# AS3364_DG412_bus_mixer_v1_3.net
KiCad netlist of a schematic drawn in EAGLE
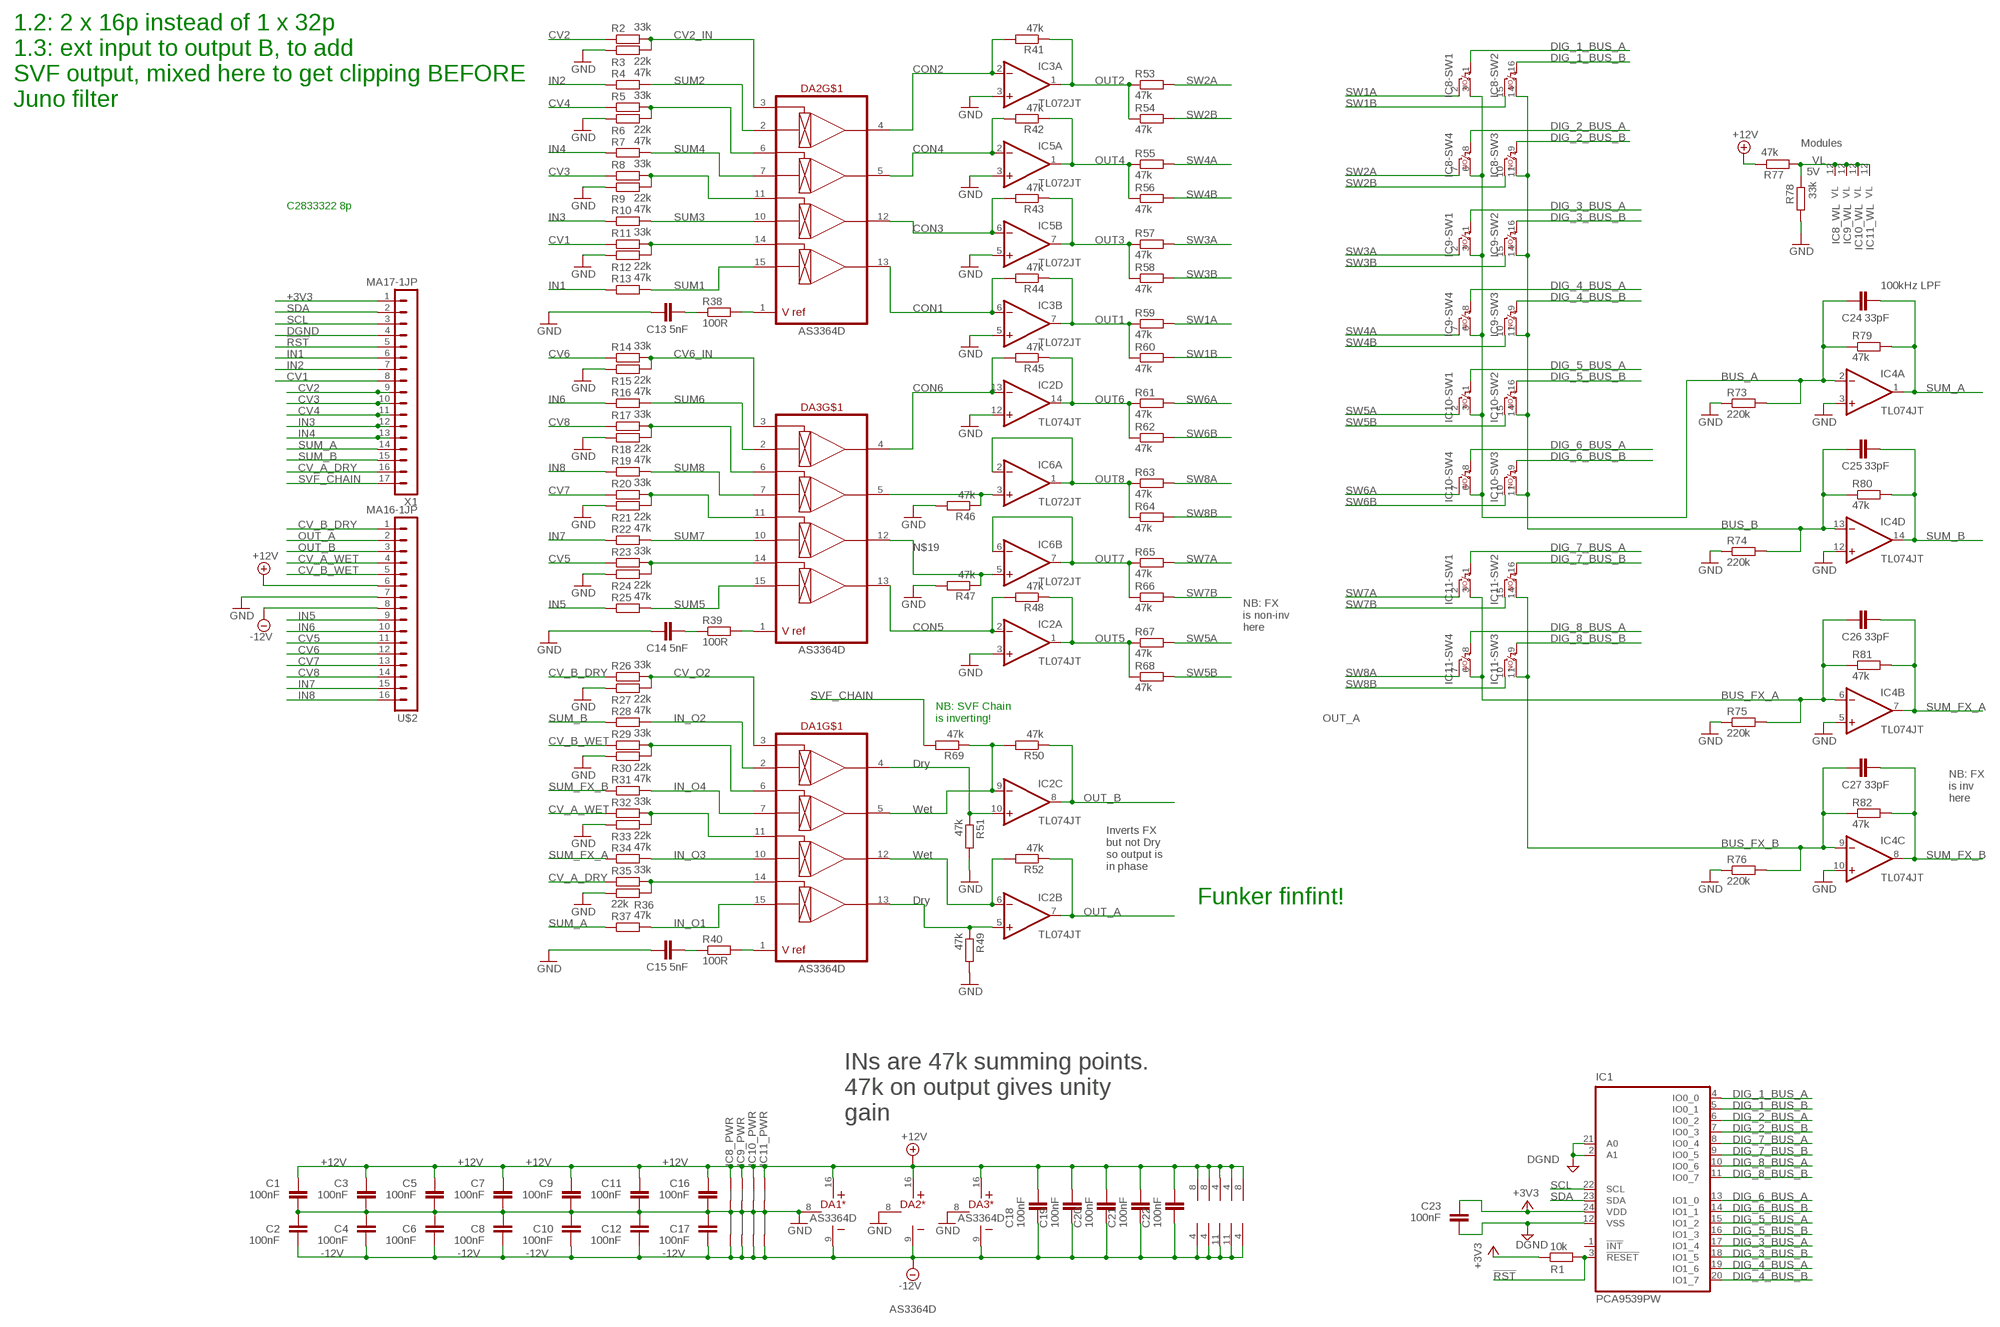
[diagram p0: schematic, sheet 1]

(export (version "E")
  (design (tool "Eeschema 10.0.6"))
  (components
    (comp (ref "C1")
      (value "100nF")
      (footprint "eagle-import:C0402")
      (libsource (lib "eagle-import") (part "C-EUC0402"))
    )
    (comp (ref "C2")
      (value "100nF")
      (footprint "eagle-import:C0402")
      (libsource (lib "eagle-import") (part "C-EUC0402"))
    )
    (comp (ref "C3")
      (value "100nF")
      (footprint "eagle-import:C0402")
      (libsource (lib "eagle-import") (part "C-EUC0402"))
    )
    (comp (ref "C4")
      (value "100nF")
      (footprint "eagle-import:C0402")
      (libsource (lib "eagle-import") (part "C-EUC0402"))
    )
    (comp (ref "C5")
      (value "100nF")
      (footprint "eagle-import:C0402")
      (libsource (lib "eagle-import") (part "C-EUC0402"))
    )
    (comp (ref "C6")
      (value "100nF")
      (footprint "eagle-import:C0402")
      (libsource (lib "eagle-import") (part "C-EUC0402"))
    )
    (comp (ref "C7")
      (value "100nF")
      (footprint "eagle-import:C0402")
      (libsource (lib "eagle-import") (part "C-EUC0402"))
    )
    (comp (ref "C8")
      (value "100nF")
      (footprint "eagle-import:C0402")
      (libsource (lib "eagle-import") (part "C-EUC0402"))
    )
    (comp (ref "C9")
      (value "100nF")
      (footprint "eagle-import:C0402")
      (libsource (lib "eagle-import") (part "C-EUC0402"))
    )
    (comp (ref "C10")
      (value "100nF")
      (footprint "eagle-import:C0402")
      (libsource (lib "eagle-import") (part "C-EUC0402"))
    )
    (comp (ref "C11")
      (value "100nF")
      (footprint "eagle-import:C0402")
      (libsource (lib "eagle-import") (part "C-EUC0402"))
    )
    (comp (ref "C12")
      (value "100nF")
      (footprint "eagle-import:C0402")
      (libsource (lib "eagle-import") (part "C-EUC0402"))
    )
    (comp (ref "C13")
      (value "5nF")
      (footprint "eagle-import:C0402-J")
      (libsource (lib "eagle-import") (part "C-EU-J"))
    )
    (comp (ref "C14")
      (value "5nF")
      (footprint "eagle-import:C0402-J")
      (libsource (lib "eagle-import") (part "C-EU-J"))
    )
    (comp (ref "C15")
      (value "5nF")
      (footprint "eagle-import:C0402-J")
      (libsource (lib "eagle-import") (part "C-EU-J"))
    )
    (comp (ref "C16")
      (value "100nF")
      (footprint "eagle-import:C0402")
      (libsource (lib "eagle-import") (part "C-EUC0402"))
    )
    (comp (ref "C17")
      (value "100nF")
      (footprint "eagle-import:C0402")
      (libsource (lib "eagle-import") (part "C-EUC0402"))
    )
    (comp (ref "C18")
      (value "100nF")
      (footprint "eagle-import:C0402")
      (libsource (lib "eagle-import") (part "C-EUC0402"))
    )
    (comp (ref "C19")
      (value "100nF")
      (footprint "eagle-import:C0402")
      (libsource (lib "eagle-import") (part "C-EUC0402"))
    )
    (comp (ref "C20")
      (value "100nF")
      (footprint "eagle-import:C0402")
      (libsource (lib "eagle-import") (part "C-EUC0402"))
    )
    (comp (ref "C21")
      (value "100nF")
      (footprint "eagle-import:C0402")
      (libsource (lib "eagle-import") (part "C-EUC0402"))
    )
    (comp (ref "C22")
      (value "100nF")
      (footprint "eagle-import:C0402")
      (libsource (lib "eagle-import") (part "C-EUC0402"))
    )
    (comp (ref "C23")
      (value "100nF")
      (footprint "eagle-import:C0402")
      (libsource (lib "eagle-import") (part "C-EUC0402"))
    )
    (comp (ref "C24")
      (value "33pF")
      (footprint "eagle-import:C0402-J")
      (libsource (lib "eagle-import") (part "C-EU-J"))
    )
    (comp (ref "C25")
      (value "33pF")
      (footprint "eagle-import:C0402-J")
      (libsource (lib "eagle-import") (part "C-EU-J"))
    )
    (comp (ref "C26")
      (value "33pF")
      (footprint "eagle-import:C0402-J")
      (libsource (lib "eagle-import") (part "C-EU-J"))
    )
    (comp (ref "C27")
      (value "33pF")
      (footprint "eagle-import:C0402-J")
      (libsource (lib "eagle-import") (part "C-EU-J"))
    )
    (comp (ref "DA1")
      (value "AS3364D")
      (footprint "eagle-import:DIL16J")
      (libsource (lib "eagle-import") (part "AS3364D"))
    )
    (comp (ref "DA2")
      (value "AS3364D")
      (footprint "eagle-import:DIL16J")
      (libsource (lib "eagle-import") (part "AS3364D"))
    )
    (comp (ref "DA3")
      (value "AS3364D")
      (footprint "eagle-import:DIL16J")
      (libsource (lib "eagle-import") (part "AS3364D"))
    )
    (comp (ref "IC1")
      (value "PCA9539PW")
      (footprint "eagle-import:TSSOP24J")
      (libsource (lib "eagle-import") (part "PCA9539PW"))
    )
    (comp (ref "IC2")
      (value "TL074JT")
      (footprint "eagle-import:TSSOP14J")
      (libsource (lib "eagle-import") (part "TL074JT"))
    )
    (comp (ref "IC3")
      (value "TL072JT")
      (footprint "eagle-import:TSSOP8J")
      (libsource (lib "eagle-import") (part "TL072JT"))
    )
    (comp (ref "IC4")
      (value "TL074JT")
      (footprint "eagle-import:TSSOP14J")
      (libsource (lib "eagle-import") (part "TL074JT"))
    )
    (comp (ref "IC5")
      (value "TL072JT")
      (footprint "eagle-import:TSSOP8J")
      (libsource (lib "eagle-import") (part "TL072JT"))
    )
    (comp (ref "IC6")
      (value "TL072JT")
      (footprint "eagle-import:TSSOP8J")
      (libsource (lib "eagle-import") (part "TL072JT"))
    )
    (comp (ref "IC8")
      (value "DG412-J")
      (footprint "eagle-import:DIL16J")
      (libsource (lib "eagle-import") (part "DG412-J"))
    )
    (comp (ref "IC9")
      (value "DG412-J")
      (footprint "eagle-import:DIL16J")
      (libsource (lib "eagle-import") (part "DG412-J"))
    )
    (comp (ref "IC10")
      (value "DG412-J")
      (footprint "eagle-import:DIL16J")
      (libsource (lib "eagle-import") (part "DG412-J"))
    )
    (comp (ref "IC11")
      (value "DG412-J")
      (footprint "eagle-import:DIL16J")
      (libsource (lib "eagle-import") (part "DG412-J"))
    )
    (comp (ref "R1")
      (value "10k")
      (footprint "eagle-import:R0402")
      (libsource (lib "eagle-import") (part "R-EU_R0402"))
    )
    (comp (ref "R2")
      (value "33k")
      (footprint "eagle-import:R0402")
      (libsource (lib "eagle-import") (part "R-EU_R0402"))
    )
    (comp (ref "R3")
      (value "22k")
      (footprint "eagle-import:R0402")
      (libsource (lib "eagle-import") (part "R-EU_R0402"))
    )
    (comp (ref "R4")
      (value "47k")
      (footprint "eagle-import:R0402")
      (libsource (lib "eagle-import") (part "R-EU_R0402"))
    )
    (comp (ref "R5")
      (value "33k")
      (footprint "eagle-import:R0402")
      (libsource (lib "eagle-import") (part "R-EU_R0402"))
    )
    (comp (ref "R6")
      (value "22k")
      (footprint "eagle-import:R0402")
      (libsource (lib "eagle-import") (part "R-EU_R0402"))
    )
    (comp (ref "R7")
      (value "47k")
      (footprint "eagle-import:R0402")
      (libsource (lib "eagle-import") (part "R-EU_R0402"))
    )
    (comp (ref "R8")
      (value "33k")
      (footprint "eagle-import:R0402")
      (libsource (lib "eagle-import") (part "R-EU_R0402"))
    )
    (comp (ref "R9")
      (value "22k")
      (footprint "eagle-import:R0402")
      (libsource (lib "eagle-import") (part "R-EU_R0402"))
    )
    (comp (ref "R10")
      (value "47k")
      (footprint "eagle-import:R0402")
      (libsource (lib "eagle-import") (part "R-EU_R0402"))
    )
    (comp (ref "R11")
      (value "33k")
      (footprint "eagle-import:R0402")
      (libsource (lib "eagle-import") (part "R-EU_R0402"))
    )
    (comp (ref "R12")
      (value "22k")
      (footprint "eagle-import:R0402")
      (libsource (lib "eagle-import") (part "R-EU_R0402"))
    )
    (comp (ref "R13")
      (value "47k")
      (footprint "eagle-import:R0402")
      (libsource (lib "eagle-import") (part "R-EU_R0402"))
    )
    (comp (ref "R14")
      (value "33k")
      (footprint "eagle-import:R0402")
      (libsource (lib "eagle-import") (part "R-EU_R0402"))
    )
    (comp (ref "R15")
      (value "22k")
      (footprint "eagle-import:R0402")
      (libsource (lib "eagle-import") (part "R-EU_R0402"))
    )
    (comp (ref "R16")
      (value "47k")
      (footprint "eagle-import:R0402")
      (libsource (lib "eagle-import") (part "R-EU_R0402"))
    )
    (comp (ref "R17")
      (value "33k")
      (footprint "eagle-import:R0402")
      (libsource (lib "eagle-import") (part "R-EU_R0402"))
    )
    (comp (ref "R18")
      (value "22k")
      (footprint "eagle-import:R0402")
      (libsource (lib "eagle-import") (part "R-EU_R0402"))
    )
    (comp (ref "R19")
      (value "47k")
      (footprint "eagle-import:R0402")
      (libsource (lib "eagle-import") (part "R-EU_R0402"))
    )
    (comp (ref "R20")
      (value "33k")
      (footprint "eagle-import:R0402")
      (libsource (lib "eagle-import") (part "R-EU_R0402"))
    )
    (comp (ref "R21")
      (value "22k")
      (footprint "eagle-import:R0402")
      (libsource (lib "eagle-import") (part "R-EU_R0402"))
    )
    (comp (ref "R22")
      (value "47k")
      (footprint "eagle-import:R0402")
      (libsource (lib "eagle-import") (part "R-EU_R0402"))
    )
    (comp (ref "R23")
      (value "33k")
      (footprint "eagle-import:R0402")
      (libsource (lib "eagle-import") (part "R-EU_R0402"))
    )
    (comp (ref "R24")
      (value "22k")
      (footprint "eagle-import:R0402")
      (libsource (lib "eagle-import") (part "R-EU_R0402"))
    )
    (comp (ref "R25")
      (value "47k")
      (footprint "eagle-import:R0402")
      (libsource (lib "eagle-import") (part "R-EU_R0402"))
    )
    (comp (ref "R26")
      (value "33k")
      (footprint "eagle-import:R0402")
      (libsource (lib "eagle-import") (part "R-EU_R0402"))
    )
    (comp (ref "R27")
      (value "22k")
      (footprint "eagle-import:R0402")
      (libsource (lib "eagle-import") (part "R-EU_R0402"))
    )
    (comp (ref "R28")
      (value "47k")
      (footprint "eagle-import:R0402")
      (libsource (lib "eagle-import") (part "R-EU_R0402"))
    )
    (comp (ref "R29")
      (value "33k")
      (footprint "eagle-import:R0402")
      (libsource (lib "eagle-import") (part "R-EU_R0402"))
    )
    (comp (ref "R30")
      (value "22k")
      (footprint "eagle-import:R0402")
      (libsource (lib "eagle-import") (part "R-EU_R0402"))
    )
    (comp (ref "R31")
      (value "47k")
      (footprint "eagle-import:R0402")
      (libsource (lib "eagle-import") (part "R-EU_R0402"))
    )
    (comp (ref "R32")
      (value "33k")
      (footprint "eagle-import:R0402")
      (libsource (lib "eagle-import") (part "R-EU_R0402"))
    )
    (comp (ref "R33")
      (value "22k")
      (footprint "eagle-import:R0402")
      (libsource (lib "eagle-import") (part "R-EU_R0402"))
    )
    (comp (ref "R34")
      (value "47k")
      (footprint "eagle-import:R0402")
      (libsource (lib "eagle-import") (part "R-EU_R0402"))
    )
    (comp (ref "R35")
      (value "33k")
      (footprint "eagle-import:R0402")
      (libsource (lib "eagle-import") (part "R-EU_R0402"))
    )
    (comp (ref "R36")
      (value "22k")
      (footprint "eagle-import:R0402")
      (libsource (lib "eagle-import") (part "R-EU_R0402"))
    )
    (comp (ref "R37")
      (value "47k")
      (footprint "eagle-import:R0402")
      (libsource (lib "eagle-import") (part "R-EU_R0402"))
    )
    (comp (ref "R38")
      (value "100R")
      (footprint "eagle-import:R0402")
      (libsource (lib "eagle-import") (part "R-EU_R0402"))
    )
    (comp (ref "R39")
      (value "100R")
      (footprint "eagle-import:R0402")
      (libsource (lib "eagle-import") (part "R-EU_R0402"))
    )
    (comp (ref "R40")
      (value "100R")
      (footprint "eagle-import:R0402")
      (libsource (lib "eagle-import") (part "R-EU_R0402"))
    )
    (comp (ref "R41")
      (value "47k")
      (footprint "eagle-import:R0402")
      (libsource (lib "eagle-import") (part "R-EU_R0402"))
    )
    (comp (ref "R42")
      (value "47k")
      (footprint "eagle-import:R0402")
      (libsource (lib "eagle-import") (part "R-EU_R0402"))
    )
    (comp (ref "R43")
      (value "47k")
      (footprint "eagle-import:R0402")
      (libsource (lib "eagle-import") (part "R-EU_R0402"))
    )
    (comp (ref "R44")
      (value "47k")
      (footprint "eagle-import:R0402")
      (libsource (lib "eagle-import") (part "R-EU_R0402"))
    )
    (comp (ref "R45")
      (value "47k")
      (footprint "eagle-import:R0402")
      (libsource (lib "eagle-import") (part "R-EU_R0402"))
    )
    (comp (ref "R46")
      (value "47k")
      (footprint "eagle-import:R0402")
      (libsource (lib "eagle-import") (part "R-EU_R0402"))
    )
    (comp (ref "R47")
      (value "47k")
      (footprint "eagle-import:R0402")
      (libsource (lib "eagle-import") (part "R-EU_R0402"))
    )
    (comp (ref "R48")
      (value "47k")
      (footprint "eagle-import:R0402")
      (libsource (lib "eagle-import") (part "R-EU_R0402"))
    )
    (comp (ref "R49")
      (value "47k")
      (footprint "eagle-import:R0402")
      (libsource (lib "eagle-import") (part "R-EU_R0402"))
    )
    (comp (ref "R50")
      (value "47k")
      (footprint "eagle-import:R0402")
      (libsource (lib "eagle-import") (part "R-EU_R0402"))
    )
    (comp (ref "R51")
      (value "47k")
      (footprint "eagle-import:R0402")
      (libsource (lib "eagle-import") (part "R-EU_R0402"))
    )
    (comp (ref "R52")
      (value "47k")
      (footprint "eagle-import:R0402")
      (libsource (lib "eagle-import") (part "R-EU_R0402"))
    )
    (comp (ref "R53")
      (value "47k")
      (footprint "eagle-import:R0402")
      (libsource (lib "eagle-import") (part "R-EU_R0402"))
    )
    (comp (ref "R54")
      (value "47k")
      (footprint "eagle-import:R0402")
      (libsource (lib "eagle-import") (part "R-EU_R0402"))
    )
    (comp (ref "R55")
      (value "47k")
      (footprint "eagle-import:R0402")
      (libsource (lib "eagle-import") (part "R-EU_R0402"))
    )
    (comp (ref "R56")
      (value "47k")
      (footprint "eagle-import:R0402")
      (libsource (lib "eagle-import") (part "R-EU_R0402"))
    )
    (comp (ref "R57")
      (value "47k")
      (footprint "eagle-import:R0402")
      (libsource (lib "eagle-import") (part "R-EU_R0402"))
    )
    (comp (ref "R58")
      (value "47k")
      (footprint "eagle-import:R0402")
      (libsource (lib "eagle-import") (part "R-EU_R0402"))
    )
    (comp (ref "R59")
      (value "47k")
      (footprint "eagle-import:R0402")
      (libsource (lib "eagle-import") (part "R-EU_R0402"))
    )
    (comp (ref "R60")
      (value "47k")
      (footprint "eagle-import:R0402")
      (libsource (lib "eagle-import") (part "R-EU_R0402"))
    )
    (comp (ref "R61")
      (value "47k")
      (footprint "eagle-import:R0402")
      (libsource (lib "eagle-import") (part "R-EU_R0402"))
    )
    (comp (ref "R62")
      (value "47k")
      (footprint "eagle-import:R0402")
      (libsource (lib "eagle-import") (part "R-EU_R0402"))
    )
    (comp (ref "R63")
      (value "47k")
      (footprint "eagle-import:R0402")
      (libsource (lib "eagle-import") (part "R-EU_R0402"))
    )
    (comp (ref "R64")
      (value "47k")
      (footprint "eagle-import:R0402")
      (libsource (lib "eagle-import") (part "R-EU_R0402"))
    )
    (comp (ref "R65")
      (value "47k")
      (footprint "eagle-import:R0402")
      (libsource (lib "eagle-import") (part "R-EU_R0402"))
    )
    (comp (ref "R66")
      (value "47k")
      (footprint "eagle-import:R0402")
      (libsource (lib "eagle-import") (part "R-EU_R0402"))
    )
    (comp (ref "R67")
      (value "47k")
      (footprint "eagle-import:R0402")
      (libsource (lib "eagle-import") (part "R-EU_R0402"))
    )
    (comp (ref "R68")
      (value "47k")
      (footprint "eagle-import:R0402")
      (libsource (lib "eagle-import") (part "R-EU_R0402"))
    )
    (comp (ref "R69")
      (value "47k")
      (footprint "eagle-import:R0402")
      (libsource (lib "eagle-import") (part "R-EU_R0402"))
    )
    (comp (ref "R73")
      (value "220k")
      (footprint "eagle-import:R0402")
      (libsource (lib "eagle-import") (part "R-EU_R0402"))
    )
    (comp (ref "R74")
      (value "220k")
      (footprint "eagle-import:R0402")
      (libsource (lib "eagle-import") (part "R-EU_R0402"))
    )
    (comp (ref "R75")
      (value "220k")
      (footprint "eagle-import:R0402")
      (libsource (lib "eagle-import") (part "R-EU_R0402"))
    )
    (comp (ref "R76")
      (value "220k")
      (footprint "eagle-import:R0402")
      (libsource (lib "eagle-import") (part "R-EU_R0402"))
    )
    (comp (ref "R77")
      (value "47k")
      (footprint "eagle-import:R0402")
      (libsource (lib "eagle-import") (part "R-EU_R0402"))
    )
    (comp (ref "R78")
      (value "33k")
      (footprint "eagle-import:R0402")
      (libsource (lib "eagle-import") (part "R-EU_R0402"))
    )
    (comp (ref "R79")
      (value "47k")
      (footprint "eagle-import:R0402")
      (libsource (lib "eagle-import") (part "R-EU_R0402"))
    )
    (comp (ref "R80")
      (value "47k")
      (footprint "eagle-import:R0402")
      (libsource (lib "eagle-import") (part "R-EU_R0402"))
    )
    (comp (ref "R81")
      (value "47k")
      (footprint "eagle-import:R0402")
      (libsource (lib "eagle-import") (part "R-EU_R0402"))
    )
    (comp (ref "R82")
      (value "47k")
      (footprint "eagle-import:R0402")
      (libsource (lib "eagle-import") (part "R-EU_R0402"))
    )
    (comp (ref "U$2")
      (value "MA16-1JP")
      (footprint "eagle-import:SIP-PIN16-1J")
      (libsource (lib "eagle-import") (part "MA16-1JP"))
    )
    (comp (ref "X1")
      (value "MA17-1JP")
      (footprint "eagle-import:SIP-PIN17-1J")
      (libsource (lib "eagle-import") (part "MA17-1JP"))
    )
  )
  (nets
    (net (code "1") (name "+3V3") (class "Default")
      (node (ref "C23") (pin "2") (pinfunction "2_2") (pintype "passive"))
      (node (ref "IC1") (pin "24") (pinfunction "VDD_24") (pintype "power_in"))
      (node (ref "R1") (pin "1") (pinfunction "1_1") (pintype "passive"))
      (node (ref "X1") (pin "1") (pinfunction "1_1") (pintype "passive"))
    )
    (net (code "2") (name "+12V") (class "Default")
      (node (ref "C1") (pin "2") (pinfunction "2_2") (pintype "passive"))
      (node (ref "C11") (pin "2") (pinfunction "2_2") (pintype "passive"))
      (node (ref "C16") (pin "2") (pinfunction "2_2") (pintype "passive"))
      (node (ref "C18") (pin "2") (pinfunction "2_2") (pintype "passive"))
      (node (ref "C19") (pin "2") (pinfunction "2_2") (pintype "passive"))
      (node (ref "C20") (pin "2") (pinfunction "2_2") (pintype "passive"))
      (node (ref "C21") (pin "2") (pinfunction "2_2") (pintype "passive"))
      (node (ref "C22") (pin "2") (pinfunction "2_2") (pintype "passive"))
      (node (ref "C3") (pin "2") (pinfunction "2_2") (pintype "passive"))
      (node (ref "C5") (pin "2") (pinfunction "2_2") (pintype "passive"))
      (node (ref "C7") (pin "2") (pinfunction "2_2") (pintype "passive"))
      (node (ref "C9") (pin "2") (pinfunction "2_2") (pintype "passive"))
      (node (ref "DA1") (pin "16") (pinfunction "V+_16") (pintype "power_in"))
      (node (ref "DA2") (pin "16") (pinfunction "V+_16") (pintype "power_in"))
      (node (ref "DA3") (pin "16") (pinfunction "V+_16") (pintype "power_in"))
      (node (ref "IC10") (pin "13") (pinfunction "+15V_13") (pintype "power_in"))
      (node (ref "IC11") (pin "13") (pinfunction "+15V_13") (pintype "power_in"))
      (node (ref "IC2") (pin "4") (pinfunction "V+_4") (pintype "power_in"))
      (node (ref "IC3") (pin "8") (pinfunction "V+_8") (pintype "power_in"))
      (node (ref "IC4") (pin "4") (pinfunction "V+_4") (pintype "power_in"))
      (node (ref "IC5") (pin "8") (pinfunction "V+_8") (pintype "power_in"))
      (node (ref "IC6") (pin "8") (pinfunction "V+_8") (pintype "power_in"))
      (node (ref "IC8") (pin "13") (pinfunction "+15V_13") (pintype "power_in"))
      (node (ref "IC9") (pin "13") (pinfunction "+15V_13") (pintype "power_in"))
      (node (ref "R77") (pin "1") (pinfunction "1_1") (pintype "passive"))
      (node (ref "U$2") (pin "6") (pinfunction "6_6") (pintype "passive"))
    )
    (net (code "3") (name "-12V") (class "Default")
      (node (ref "C10") (pin "1") (pinfunction "1_1") (pintype "passive"))
      (node (ref "C12") (pin "1") (pinfunction "1_1") (pintype "passive"))
      (node (ref "C17") (pin "1") (pinfunction "1_1") (pintype "passive"))
      (node (ref "C18") (pin "1") (pinfunction "1_1") (pintype "passive"))
      (node (ref "C19") (pin "1") (pinfunction "1_1") (pintype "passive"))
      (node (ref "C2") (pin "1") (pinfunction "1_1") (pintype "passive"))
      (node (ref "C20") (pin "1") (pinfunction "1_1") (pintype "passive"))
      (node (ref "C21") (pin "1") (pinfunction "1_1") (pintype "passive"))
      (node (ref "C22") (pin "1") (pinfunction "1_1") (pintype "passive"))
      (node (ref "C4") (pin "1") (pinfunction "1_1") (pintype "passive"))
      (node (ref "C6") (pin "1") (pinfunction "1_1") (pintype "passive"))
      (node (ref "C8") (pin "1") (pinfunction "1_1") (pintype "passive"))
      (node (ref "DA1") (pin "9") (pinfunction "V-_9") (pintype "power_in"))
      (node (ref "DA2") (pin "9") (pinfunction "V-_9") (pintype "power_in"))
      (node (ref "DA3") (pin "9") (pinfunction "V-_9") (pintype "power_in"))
      (node (ref "IC10") (pin "4") (pinfunction "-15V_4") (pintype "power_in"))
      (node (ref "IC11") (pin "4") (pinfunction "-15V_4") (pintype "power_in"))
      (node (ref "IC2") (pin "11") (pinfunction "V-_11") (pintype "power_in"))
      (node (ref "IC3") (pin "4") (pinfunction "V-_4") (pintype "power_in"))
      (node (ref "IC4") (pin "11") (pinfunction "V-_11") (pintype "power_in"))
      (node (ref "IC5") (pin "4") (pinfunction "V-_4") (pintype "power_in"))
      (node (ref "IC6") (pin "4") (pinfunction "V-_4") (pintype "power_in"))
      (node (ref "IC8") (pin "4") (pinfunction "-15V_4") (pintype "power_in"))
      (node (ref "IC9") (pin "4") (pinfunction "-15V_4") (pintype "power_in"))
      (node (ref "U$2") (pin "8") (pinfunction "8_8") (pintype "passive"))
    )
    (net (code "4") (name "/BUS_A") (class "Default")
      (node (ref "C24") (pin "1") (pinfunction "1_1") (pintype "passive"))
      (node (ref "IC10") (pin "3") (pinfunction "S_3") (pintype "bidirectional"))
      (node (ref "IC10") (pin "6") (pinfunction "S_6") (pintype "bidirectional"))
      (node (ref "IC4") (pin "2") (pinfunction "-IN_2") (pintype "input"))
      (node (ref "IC8") (pin "3") (pinfunction "S_3") (pintype "bidirectional"))
      (node (ref "IC8") (pin "6") (pinfunction "S_6") (pintype "bidirectional"))
      (node (ref "IC9") (pin "3") (pinfunction "S_3") (pintype "bidirectional"))
      (node (ref "IC9") (pin "6") (pinfunction "S_6") (pintype "bidirectional"))
      (node (ref "R73") (pin "2") (pinfunction "2_2") (pintype "passive"))
      (node (ref "R79") (pin "1") (pinfunction "1_1") (pintype "passive"))
    )
    (net (code "5") (name "/BUS_B") (class "Default")
      (node (ref "C25") (pin "1") (pinfunction "1_1") (pintype "passive"))
      (node (ref "IC10") (pin "11") (pinfunction "S_11") (pintype "bidirectional"))
      (node (ref "IC10") (pin "14") (pinfunction "S_14") (pintype "bidirectional"))
      (node (ref "IC4") (pin "13") (pinfunction "-IN_13") (pintype "input"))
      (node (ref "IC8") (pin "11") (pinfunction "S_11") (pintype "bidirectional"))
      (node (ref "IC8") (pin "14") (pinfunction "S_14") (pintype "bidirectional"))
      (node (ref "IC9") (pin "11") (pinfunction "S_11") (pintype "bidirectional"))
      (node (ref "IC9") (pin "14") (pinfunction "S_14") (pintype "bidirectional"))
      (node (ref "R74") (pin "2") (pinfunction "2_2") (pintype "passive"))
      (node (ref "R80") (pin "1") (pinfunction "1_1") (pintype "passive"))
    )
    (net (code "6") (name "/BUS_FX_A") (class "Default")
      (node (ref "C26") (pin "1") (pinfunction "1_1") (pintype "passive"))
      (node (ref "IC11") (pin "3") (pinfunction "S_3") (pintype "bidirectional"))
      (node (ref "IC11") (pin "6") (pinfunction "S_6") (pintype "bidirectional"))
      (node (ref "IC4") (pin "6") (pinfunction "-IN_6") (pintype "input"))
      (node (ref "R75") (pin "2") (pinfunction "2_2") (pintype "passive"))
      (node (ref "R81") (pin "1") (pinfunction "1_1") (pintype "passive"))
    )
    (net (code "7") (name "/BUS_FX_B") (class "Default")
      (node (ref "C27") (pin "1") (pinfunction "1_1") (pintype "passive"))
      (node (ref "IC11") (pin "11") (pinfunction "S_11") (pintype "bidirectional"))
      (node (ref "IC11") (pin "14") (pinfunction "S_14") (pintype "bidirectional"))
      (node (ref "IC4") (pin "9") (pinfunction "-IN_9") (pintype "input"))
      (node (ref "R76") (pin "2") (pinfunction "2_2") (pintype "passive"))
      (node (ref "R82") (pin "1") (pinfunction "1_1") (pintype "passive"))
    )
    (net (code "8") (name "/CON1") (class "Default")
      (node (ref "DA2") (pin "13") (pinfunction "OUT4_13") (pintype "output"))
      (node (ref "IC3") (pin "6") (pinfunction "-IN_6") (pintype "input"))
      (node (ref "R44") (pin "2") (pinfunction "2_2") (pintype "passive"))
    )
    (net (code "9") (name "/CON2") (class "Default")
      (node (ref "DA2") (pin "4") (pinfunction "OUT1_4") (pintype "output"))
      (node (ref "IC3") (pin "2") (pinfunction "-IN_2") (pintype "input"))
      (node (ref "R41") (pin "2") (pinfunction "2_2") (pintype "passive"))
    )
    (net (code "10") (name "/CON3") (class "Default")
      (node (ref "DA2") (pin "12") (pinfunction "OUT3_12") (pintype "output"))
      (node (ref "IC5") (pin "6") (pinfunction "-IN_6") (pintype "input"))
      (node (ref "R43") (pin "2") (pinfunction "2_2") (pintype "passive"))
    )
    (net (code "11") (name "/CON4") (class "Default")
      (node (ref "DA2") (pin "5") (pinfunction "OUT2_5") (pintype "output"))
      (node (ref "IC5") (pin "2") (pinfunction "-IN_2") (pintype "input"))
      (node (ref "R42") (pin "2") (pinfunction "2_2") (pintype "passive"))
    )
    (net (code "12") (name "/CON5") (class "Default")
      (node (ref "DA3") (pin "13") (pinfunction "OUT4_13") (pintype "output"))
      (node (ref "IC2") (pin "2") (pinfunction "-IN_2") (pintype "input"))
      (node (ref "R48") (pin "2") (pinfunction "2_2") (pintype "passive"))
    )
    (net (code "13") (name "/CON6") (class "Default")
      (node (ref "DA3") (pin "4") (pinfunction "OUT1_4") (pintype "output"))
      (node (ref "IC2") (pin "13") (pinfunction "-IN_13") (pintype "input"))
      (node (ref "R45") (pin "2") (pinfunction "2_2") (pintype "passive"))
    )
    (net (code "14") (name "/CV1") (class "Default")
      (node (ref "R11") (pin "1") (pinfunction "1_1") (pintype "passive"))
      (node (ref "X1") (pin "8") (pinfunction "8_8") (pintype "passive"))
    )
    (net (code "15") (name "/CV2") (class "Default")
      (node (ref "R2") (pin "1") (pinfunction "1_1") (pintype "passive"))
      (node (ref "X1") (pin "9") (pinfunction "9_9") (pintype "passive"))
    )
    (net (code "16") (name "/CV2_IN") (class "Default")
      (node (ref "DA2") (pin "3") (pinfunction "CV1_3") (pintype "input"))
      (node (ref "R2") (pin "2") (pinfunction "2_2") (pintype "passive"))
      (node (ref "R3") (pin "2") (pinfunction "2_2") (pintype "passive"))
    )
    (net (code "17") (name "/CV3") (class "Default")
      (node (ref "R8") (pin "1") (pinfunction "1_1") (pintype "passive"))
      (node (ref "X1") (pin "10") (pinfunction "10_10") (pintype "passive"))
    )
    (net (code "18") (name "/CV4") (class "Default")
      (node (ref "R5") (pin "1") (pinfunction "1_1") (pintype "passive"))
      (node (ref "X1") (pin "11") (pinfunction "11_11") (pintype "passive"))
    )
    (net (code "19") (name "/CV5") (class "Default")
      (node (ref "R23") (pin "1") (pinfunction "1_1") (pintype "passive"))
      (node (ref "U$2") (pin "11") (pinfunction "11_11") (pintype "passive"))
    )
    (net (code "20") (name "/CV6") (class "Default")
      (node (ref "R14") (pin "1") (pinfunction "1_1") (pintype "passive"))
      (node (ref "U$2") (pin "12") (pinfunction "12_12") (pintype "passive"))
    )
    (net (code "21") (name "/CV6_IN") (class "Default")
      (node (ref "DA3") (pin "3") (pinfunction "CV1_3") (pintype "input"))
      (node (ref "R14") (pin "2") (pinfunction "2_2") (pintype "passive"))
      (node (ref "R15") (pin "2") (pinfunction "2_2") (pintype "passive"))
    )
    (net (code "22") (name "/CV7") (class "Default")
      (node (ref "R20") (pin "1") (pinfunction "1_1") (pintype "passive"))
      (node (ref "U$2") (pin "13") (pinfunction "13_13") (pintype "passive"))
    )
    (net (code "23") (name "/CV8") (class "Default")
      (node (ref "R17") (pin "1") (pinfunction "1_1") (pintype "passive"))
      (node (ref "U$2") (pin "14") (pinfunction "14_14") (pintype "passive"))
    )
    (net (code "24") (name "/CV_A_DRY") (class "Default")
      (node (ref "R35") (pin "1") (pinfunction "1_1") (pintype "passive"))
      (node (ref "X1") (pin "16") (pinfunction "16_16") (pintype "passive"))
    )
    (net (code "25") (name "/CV_A_WET") (class "Default")
      (node (ref "R32") (pin "1") (pinfunction "1_1") (pintype "passive"))
      (node (ref "U$2") (pin "4") (pinfunction "4_4") (pintype "passive"))
    )
    (net (code "26") (name "/CV_B_DRY") (class "Default")
      (node (ref "R26") (pin "1") (pinfunction "1_1") (pintype "passive"))
      (node (ref "U$2") (pin "1") (pinfunction "1_1") (pintype "passive"))
    )
    (net (code "27") (name "/CV_B_WET") (class "Default")
      (node (ref "R29") (pin "1") (pinfunction "1_1") (pintype "passive"))
      (node (ref "U$2") (pin "5") (pinfunction "5_5") (pintype "passive"))
    )
    (net (code "28") (name "/CV_O2") (class "Default")
      (node (ref "DA1") (pin "3") (pinfunction "CV1_3") (pintype "input"))
      (node (ref "R26") (pin "2") (pinfunction "2_2") (pintype "passive"))
      (node (ref "R27") (pin "2") (pinfunction "2_2") (pintype "passive"))
    )
    (net (code "29") (name "/DIG_1_BUS_A") (class "Default")
      (node (ref "IC1") (pin "4") (pinfunction "IO0_0_4") (pintype "bidirectional"))
      (node (ref "IC8") (pin "1") (pinfunction "C_1") (pintype "bidirectional"))
    )
    (net (code "30") (name "/DIG_1_BUS_B") (class "Default")
      (node (ref "IC1") (pin "5") (pinfunction "IO0_1_5") (pintype "bidirectional"))
      (node (ref "IC8") (pin "16") (pinfunction "C_16") (pintype "bidirectional"))
    )
    (net (code "31") (name "/DIG_2_BUS_A") (class "Default")
      (node (ref "IC1") (pin "6") (pinfunction "IO0_2_6") (pintype "bidirectional"))
      (node (ref "IC8") (pin "8") (pinfunction "C_8") (pintype "bidirectional"))
    )
    (net (code "32") (name "/DIG_2_BUS_B") (class "Default")
      (node (ref "IC1") (pin "7") (pinfunction "IO0_3_7") (pintype "bidirectional"))
      (node (ref "IC8") (pin "9") (pinfunction "C_9") (pintype "bidirectional"))
    )
    (net (code "33") (name "/DIG_3_BUS_A") (class "Default")
      (node (ref "IC1") (pin "17") (pinfunction "IO1_4_17") (pintype "bidirectional"))
      (node (ref "IC9") (pin "1") (pinfunction "C_1") (pintype "bidirectional"))
    )
    (net (code "34") (name "/DIG_3_BUS_B") (class "Default")
      (node (ref "IC1") (pin "18") (pinfunction "IO1_5_18") (pintype "bidirectional"))
      (node (ref "IC9") (pin "16") (pinfunction "C_16") (pintype "bidirectional"))
    )
    (net (code "35") (name "/DIG_4_BUS_A") (class "Default")
      (node (ref "IC1") (pin "19") (pinfunction "IO1_6_19") (pintype "bidirectional"))
      (node (ref "IC9") (pin "8") (pinfunction "C_8") (pintype "bidirectional"))
    )
    (net (code "36") (name "/DIG_4_BUS_B") (class "Default")
      (node (ref "IC1") (pin "20") (pinfunction "IO1_7_20") (pintype "bidirectional"))
      (node (ref "IC9") (pin "9") (pinfunction "C_9") (pintype "bidirectional"))
    )
    (net (code "37") (name "/DIG_5_BUS_A") (class "Default")
      (node (ref "IC1") (pin "15") (pinfunction "IO1_2_15") (pintype "bidirectional"))
      (node (ref "IC10") (pin "1") (pinfunction "C_1") (pintype "bidirectional"))
    )
    (net (code "38") (name "/DIG_5_BUS_B") (class "Default")
      (node (ref "IC1") (pin "16") (pinfunction "IO1_3_16") (pintype "bidirectional"))
      (node (ref "IC10") (pin "16") (pinfunction "C_16") (pintype "bidirectional"))
    )
    (net (code "39") (name "/DIG_6_BUS_A") (class "Default")
      (node (ref "IC1") (pin "13") (pinfunction "IO1_0_13") (pintype "bidirectional"))
      (node (ref "IC10") (pin "8") (pinfunction "C_8") (pintype "bidirectional"))
    )
    (net (code "40") (name "/DIG_6_BUS_B") (class "Default")
      (node (ref "IC1") (pin "14") (pinfunction "IO1_1_14") (pintype "bidirectional"))
      (node (ref "IC10") (pin "9") (pinfunction "C_9") (pintype "bidirectional"))
    )
    (net (code "41") (name "/DIG_7_BUS_A") (class "Default")
      (node (ref "IC1") (pin "8") (pinfunction "IO0_4_8") (pintype "bidirectional"))
      (node (ref "IC11") (pin "1") (pinfunction "C_1") (pintype "bidirectional"))
    )
    (net (code "42") (name "/DIG_7_BUS_B") (class "Default")
      (node (ref "IC1") (pin "9") (pinfunction "IO0_5_9") (pintype "bidirectional"))
      (node (ref "IC11") (pin "16") (pinfunction "C_16") (pintype "bidirectional"))
    )
    (net (code "43") (name "/DIG_8_BUS_A") (class "Default")
      (node (ref "IC1") (pin "10") (pinfunction "IO0_6_10") (pintype "bidirectional"))
      (node (ref "IC11") (pin "8") (pinfunction "C_8") (pintype "bidirectional"))
    )
    (net (code "44") (name "/DIG_8_BUS_B") (class "Default")
      (node (ref "IC1") (pin "11") (pinfunction "IO0_7_11") (pintype "bidirectional"))
      (node (ref "IC11") (pin "9") (pinfunction "C_9") (pintype "bidirectional"))
    )
    (net (code "45") (name "/IN1") (class "Default")
      (node (ref "R13") (pin "1") (pinfunction "1_1") (pintype "passive"))
      (node (ref "X1") (pin "6") (pinfunction "6_6") (pintype "passive"))
    )
    (net (code "46") (name "/IN2") (class "Default")
      (node (ref "R4") (pin "1") (pinfunction "1_1") (pintype "passive"))
      (node (ref "X1") (pin "7") (pinfunction "7_7") (pintype "passive"))
    )
    (net (code "47") (name "/IN3") (class "Default")
      (node (ref "R10") (pin "1") (pinfunction "1_1") (pintype "passive"))
      (node (ref "X1") (pin "12") (pinfunction "12_12") (pintype "passive"))
    )
    (net (code "48") (name "/IN4") (class "Default")
      (node (ref "R7") (pin "1") (pinfunction "1_1") (pintype "passive"))
      (node (ref "X1") (pin "13") (pinfunction "13_13") (pintype "passive"))
    )
    (net (code "49") (name "/IN5") (class "Default")
      (node (ref "R25") (pin "1") (pinfunction "1_1") (pintype "passive"))
      (node (ref "U$2") (pin "9") (pinfunction "9_9") (pintype "passive"))
    )
    (net (code "50") (name "/IN6") (class "Default")
      (node (ref "R16") (pin "1") (pinfunction "1_1") (pintype "passive"))
      (node (ref "U$2") (pin "10") (pinfunction "10_10") (pintype "passive"))
    )
    (net (code "51") (name "/IN7") (class "Default")
      (node (ref "R22") (pin "1") (pinfunction "1_1") (pintype "passive"))
      (node (ref "U$2") (pin "15") (pinfunction "15_15") (pintype "passive"))
    )
    (net (code "52") (name "/IN8") (class "Default")
      (node (ref "R19") (pin "1") (pinfunction "1_1") (pintype "passive"))
      (node (ref "U$2") (pin "16") (pinfunction "16_16") (pintype "passive"))
    )
    (net (code "53") (name "/IN_O1") (class "Default")
      (node (ref "DA1") (pin "15") (pinfunction "IN4_15") (pintype "input"))
      (node (ref "R37") (pin "2") (pinfunction "2_2") (pintype "passive"))
    )
    (net (code "54") (name "/IN_O2") (class "Default")
      (node (ref "DA1") (pin "2") (pinfunction "IN1_2") (pintype "input"))
      (node (ref "R28") (pin "2") (pinfunction "2_2") (pintype "passive"))
    )
    (net (code "55") (name "/IN_O3") (class "Default")
      (node (ref "DA1") (pin "10") (pinfunction "IN3_10") (pintype "input"))
      (node (ref "R34") (pin "2") (pinfunction "2_2") (pintype "passive"))
    )
    (net (code "56") (name "/IN_O4") (class "Default")
      (node (ref "DA1") (pin "7") (pinfunction "IN2_7") (pintype "input"))
      (node (ref "R31") (pin "2") (pinfunction "2_2") (pintype "passive"))
    )
    (net (code "57") (name "/N$19") (class "Default")
      (node (ref "DA3") (pin "12") (pinfunction "OUT3_12") (pintype "output"))
      (node (ref "IC6") (pin "5") (pinfunction "+IN_5") (pintype "input"))
      (node (ref "R47") (pin "1") (pinfunction "1_1") (pintype "passive"))
    )
    (net (code "58") (name "/OUT1") (class "Default")
      (node (ref "IC3") (pin "7") (pinfunction "OUT_7") (pintype "output"))
      (node (ref "R44") (pin "1") (pinfunction "1_1") (pintype "passive"))
      (node (ref "R59") (pin "1") (pinfunction "1_1") (pintype "passive"))
      (node (ref "R60") (pin "1") (pinfunction "1_1") (pintype "passive"))
    )
    (net (code "59") (name "/OUT2") (class "Default")
      (node (ref "IC3") (pin "1") (pinfunction "OUT_1") (pintype "output"))
      (node (ref "R41") (pin "1") (pinfunction "1_1") (pintype "passive"))
      (node (ref "R53") (pin "1") (pinfunction "1_1") (pintype "passive"))
      (node (ref "R54") (pin "1") (pinfunction "1_1") (pintype "passive"))
    )
    (net (code "60") (name "/OUT3") (class "Default")
      (node (ref "IC5") (pin "7") (pinfunction "OUT_7") (pintype "output"))
      (node (ref "R43") (pin "1") (pinfunction "1_1") (pintype "passive"))
      (node (ref "R57") (pin "1") (pinfunction "1_1") (pintype "passive"))
      (node (ref "R58") (pin "1") (pinfunction "1_1") (pintype "passive"))
    )
    (net (code "61") (name "/OUT4") (class "Default")
      (node (ref "IC5") (pin "1") (pinfunction "OUT_1") (pintype "output"))
      (node (ref "R42") (pin "1") (pinfunction "1_1") (pintype "passive"))
      (node (ref "R55") (pin "1") (pinfunction "1_1") (pintype "passive"))
      (node (ref "R56") (pin "1") (pinfunction "1_1") (pintype "passive"))
    )
    (net (code "62") (name "/OUT5") (class "Default")
      (node (ref "IC2") (pin "1") (pinfunction "OUT_1") (pintype "output"))
      (node (ref "R48") (pin "1") (pinfunction "1_1") (pintype "passive"))
      (node (ref "R67") (pin "1") (pinfunction "1_1") (pintype "passive"))
      (node (ref "R68") (pin "1") (pinfunction "1_1") (pintype "passive"))
    )
    (net (code "63") (name "/OUT6") (class "Default")
      (node (ref "IC2") (pin "14") (pinfunction "OUT_14") (pintype "output"))
      (node (ref "R45") (pin "1") (pinfunction "1_1") (pintype "passive"))
      (node (ref "R61") (pin "1") (pinfunction "1_1") (pintype "passive"))
      (node (ref "R62") (pin "1") (pinfunction "1_1") (pintype "passive"))
    )
    (net (code "64") (name "/OUT7") (class "Default")
      (node (ref "IC6") (pin "6") (pinfunction "-IN_6") (pintype "input"))
      (node (ref "IC6") (pin "7") (pinfunction "OUT_7") (pintype "output"))
      (node (ref "R65") (pin "1") (pinfunction "1_1") (pintype "passive"))
      (node (ref "R66") (pin "1") (pinfunction "1_1") (pintype "passive"))
    )
    (net (code "65") (name "/OUT8") (class "Default")
      (node (ref "IC6") (pin "1") (pinfunction "OUT_1") (pintype "output"))
      (node (ref "IC6") (pin "2") (pinfunction "-IN_2") (pintype "input"))
      (node (ref "R63") (pin "1") (pinfunction "1_1") (pintype "passive"))
      (node (ref "R64") (pin "1") (pinfunction "1_1") (pintype "passive"))
    )
    (net (code "66") (name "/OUT_A") (class "Default")
      (node (ref "IC2") (pin "7") (pinfunction "OUT_7") (pintype "output"))
      (node (ref "R52") (pin "1") (pinfunction "1_1") (pintype "passive"))
      (node (ref "U$2") (pin "2") (pinfunction "2_2") (pintype "passive"))
    )
    (net (code "67") (name "/OUT_B") (class "Default")
      (node (ref "IC2") (pin "8") (pinfunction "OUT_8") (pintype "output"))
      (node (ref "R50") (pin "1") (pinfunction "1_1") (pintype "passive"))
      (node (ref "U$2") (pin "3") (pinfunction "3_3") (pintype "passive"))
    )
    (net (code "68") (name "/SCL") (class "Default")
      (node (ref "IC1") (pin "22") (pinfunction "SCL_22") (pintype "bidirectional"))
      (node (ref "X1") (pin "3") (pinfunction "3_3") (pintype "passive"))
    )
    (net (code "69") (name "/SDA") (class "Default")
      (node (ref "IC1") (pin "23") (pinfunction "SDA_23") (pintype "bidirectional"))
      (node (ref "X1") (pin "2") (pinfunction "2_2") (pintype "passive"))
    )
    (net (code "70") (name "/SUM1") (class "Default")
      (node (ref "DA2") (pin "15") (pinfunction "IN4_15") (pintype "input"))
      (node (ref "R13") (pin "2") (pinfunction "2_2") (pintype "passive"))
    )
    (net (code "71") (name "/SUM2") (class "Default")
      (node (ref "DA2") (pin "2") (pinfunction "IN1_2") (pintype "input"))
      (node (ref "R4") (pin "2") (pinfunction "2_2") (pintype "passive"))
    )
    (net (code "72") (name "/SUM3") (class "Default")
      (node (ref "DA2") (pin "10") (pinfunction "IN3_10") (pintype "input"))
      (node (ref "R10") (pin "2") (pinfunction "2_2") (pintype "passive"))
    )
    (net (code "73") (name "/SUM4") (class "Default")
      (node (ref "DA2") (pin "7") (pinfunction "IN2_7") (pintype "input"))
      (node (ref "R7") (pin "2") (pinfunction "2_2") (pintype "passive"))
    )
    (net (code "74") (name "/SUM5") (class "Default")
      (node (ref "DA3") (pin "15") (pinfunction "IN4_15") (pintype "input"))
      (node (ref "R25") (pin "2") (pinfunction "2_2") (pintype "passive"))
    )
    (net (code "75") (name "/SUM6") (class "Default")
      (node (ref "DA3") (pin "2") (pinfunction "IN1_2") (pintype "input"))
      (node (ref "R16") (pin "2") (pinfunction "2_2") (pintype "passive"))
    )
    (net (code "76") (name "/SUM7") (class "Default")
      (node (ref "DA3") (pin "10") (pinfunction "IN3_10") (pintype "input"))
      (node (ref "R22") (pin "2") (pinfunction "2_2") (pintype "passive"))
    )
    (net (code "77") (name "/SUM8") (class "Default")
      (node (ref "DA3") (pin "7") (pinfunction "IN2_7") (pintype "input"))
      (node (ref "R19") (pin "2") (pinfunction "2_2") (pintype "passive"))
    )
    (net (code "78") (name "/SUM_A") (class "Default")
      (node (ref "C24") (pin "2") (pinfunction "2_2") (pintype "passive"))
      (node (ref "IC4") (pin "1") (pinfunction "OUT_1") (pintype "output"))
      (node (ref "R37") (pin "1") (pinfunction "1_1") (pintype "passive"))
      (node (ref "R79") (pin "2") (pinfunction "2_2") (pintype "passive"))
      (node (ref "X1") (pin "14") (pinfunction "14_14") (pintype "passive"))
    )
    (net (code "79") (name "/SUM_B") (class "Default")
      (node (ref "C25") (pin "2") (pinfunction "2_2") (pintype "passive"))
      (node (ref "IC4") (pin "14") (pinfunction "OUT_14") (pintype "output"))
      (node (ref "R28") (pin "1") (pinfunction "1_1") (pintype "passive"))
      (node (ref "R80") (pin "2") (pinfunction "2_2") (pintype "passive"))
      (node (ref "X1") (pin "15") (pinfunction "15_15") (pintype "passive"))
    )
    (net (code "80") (name "/SUM_FX_A") (class "Default")
      (node (ref "C26") (pin "2") (pinfunction "2_2") (pintype "passive"))
      (node (ref "IC4") (pin "7") (pinfunction "OUT_7") (pintype "output"))
      (node (ref "R34") (pin "1") (pinfunction "1_1") (pintype "passive"))
      (node (ref "R81") (pin "2") (pinfunction "2_2") (pintype "passive"))
    )
    (net (code "81") (name "/SUM_FX_B") (class "Default")
      (node (ref "C27") (pin "2") (pinfunction "2_2") (pintype "passive"))
      (node (ref "IC4") (pin "8") (pinfunction "OUT_8") (pintype "output"))
      (node (ref "R31") (pin "1") (pinfunction "1_1") (pintype "passive"))
      (node (ref "R82") (pin "2") (pinfunction "2_2") (pintype "passive"))
    )
    (net (code "82") (name "/SVF_CHAIN") (class "Default")
      (node (ref "R69") (pin "2") (pinfunction "2_2") (pintype "passive"))
      (node (ref "X1") (pin "17") (pinfunction "17_17") (pintype "passive"))
    )
    (net (code "83") (name "/SW1A") (class "Default")
      (node (ref "IC8") (pin "2") (pinfunction "D_2") (pintype "bidirectional"))
      (node (ref "R59") (pin "2") (pinfunction "2_2") (pintype "passive"))
    )
    (net (code "84") (name "/SW1B") (class "Default")
      (node (ref "IC8") (pin "15") (pinfunction "D_15") (pintype "bidirectional"))
      (node (ref "R60") (pin "2") (pinfunction "2_2") (pintype "passive"))
    )
    (net (code "85") (name "/SW2A") (class "Default")
      (node (ref "IC8") (pin "7") (pinfunction "D_7") (pintype "bidirectional"))
      (node (ref "R53") (pin "2") (pinfunction "2_2") (pintype "passive"))
    )
    (net (code "86") (name "/SW2B") (class "Default")
      (node (ref "IC8") (pin "10") (pinfunction "D_10") (pintype "bidirectional"))
      (node (ref "R54") (pin "2") (pinfunction "2_2") (pintype "passive"))
    )
    (net (code "87") (name "/SW3A") (class "Default")
      (node (ref "IC9") (pin "2") (pinfunction "D_2") (pintype "bidirectional"))
      (node (ref "R57") (pin "2") (pinfunction "2_2") (pintype "passive"))
    )
    (net (code "88") (name "/SW3B") (class "Default")
      (node (ref "IC9") (pin "15") (pinfunction "D_15") (pintype "bidirectional"))
      (node (ref "R58") (pin "2") (pinfunction "2_2") (pintype "passive"))
    )
    (net (code "89") (name "/SW4A") (class "Default")
      (node (ref "IC9") (pin "7") (pinfunction "D_7") (pintype "bidirectional"))
      (node (ref "R55") (pin "2") (pinfunction "2_2") (pintype "passive"))
    )
    (net (code "90") (name "/SW4B") (class "Default")
      (node (ref "IC9") (pin "10") (pinfunction "D_10") (pintype "bidirectional"))
      (node (ref "R56") (pin "2") (pinfunction "2_2") (pintype "passive"))
    )
    (net (code "91") (name "/SW5A") (class "Default")
      (node (ref "IC10") (pin "2") (pinfunction "D_2") (pintype "bidirectional"))
      (node (ref "R67") (pin "2") (pinfunction "2_2") (pintype "passive"))
    )
    (net (code "92") (name "/SW5B") (class "Default")
      (node (ref "IC10") (pin "15") (pinfunction "D_15") (pintype "bidirectional"))
      (node (ref "R68") (pin "2") (pinfunction "2_2") (pintype "passive"))
    )
    (net (code "93") (name "/SW6A") (class "Default")
      (node (ref "IC10") (pin "7") (pinfunction "D_7") (pintype "bidirectional"))
      (node (ref "R61") (pin "2") (pinfunction "2_2") (pintype "passive"))
    )
    (net (code "94") (name "/SW6B") (class "Default")
      (node (ref "IC10") (pin "10") (pinfunction "D_10") (pintype "bidirectional"))
      (node (ref "R62") (pin "2") (pinfunction "2_2") (pintype "passive"))
    )
    (net (code "95") (name "/SW7A") (class "Default")
      (node (ref "IC11") (pin "2") (pinfunction "D_2") (pintype "bidirectional"))
      (node (ref "R65") (pin "2") (pinfunction "2_2") (pintype "passive"))
    )
    (net (code "96") (name "/SW7B") (class "Default")
      (node (ref "IC11") (pin "15") (pinfunction "D_15") (pintype "bidirectional"))
      (node (ref "R66") (pin "2") (pinfunction "2_2") (pintype "passive"))
    )
    (net (code "97") (name "/SW8A") (class "Default")
      (node (ref "IC11") (pin "7") (pinfunction "D_7") (pintype "bidirectional"))
      (node (ref "R63") (pin "2") (pinfunction "2_2") (pintype "passive"))
    )
    (net (code "98") (name "/SW8B") (class "Default")
      (node (ref "IC11") (pin "10") (pinfunction "D_10") (pintype "bidirectional"))
      (node (ref "R64") (pin "2") (pinfunction "2_2") (pintype "passive"))
    )
    (net (code "99") (name "/VL") (class "Default")
      (node (ref "IC10") (pin "12") (pinfunction "VL_12") (pintype "bidirectional"))
      (node (ref "IC11") (pin "12") (pinfunction "VL_12") (pintype "bidirectional"))
      (node (ref "IC8") (pin "12") (pinfunction "VL_12") (pintype "bidirectional"))
      (node (ref "IC9") (pin "12") (pinfunction "VL_12") (pintype "bidirectional"))
      (node (ref "R77") (pin "2") (pinfunction "2_2") (pintype "passive"))
      (node (ref "R78") (pin "1") (pinfunction "1_1") (pintype "passive"))
    )
    (net (code "100") (name "/~{RST}") (class "Default")
      (node (ref "IC1") (pin "3") (pinfunction "~{RESET}_3") (pintype "bidirectional"))
      (node (ref "R1") (pin "2") (pinfunction "2_2") (pintype "passive"))
      (node (ref "X1") (pin "5") (pinfunction "5_5") (pintype "passive"))
    )
    (net (code "101") (name "DGND") (class "Default")
      (node (ref "C23") (pin "1") (pinfunction "1_1") (pintype "passive"))
      (node (ref "IC1") (pin "12") (pinfunction "VSS_12") (pintype "power_in"))
      (node (ref "IC1") (pin "2") (pinfunction "A1_2") (pintype "bidirectional"))
      (node (ref "IC1") (pin "21") (pinfunction "A0_21") (pintype "bidirectional"))
      (node (ref "X1") (pin "4") (pinfunction "4_4") (pintype "passive"))
    )
    (net (code "102") (name "GND") (class "Default")
      (node (ref "C1") (pin "1") (pinfunction "1_1") (pintype "passive"))
      (node (ref "C10") (pin "2") (pinfunction "2_2") (pintype "passive"))
      (node (ref "C11") (pin "1") (pinfunction "1_1") (pintype "passive"))
      (node (ref "C12") (pin "2") (pinfunction "2_2") (pintype "passive"))
      (node (ref "C13") (pin "1") (pinfunction "1_1") (pintype "passive"))
      (node (ref "C14") (pin "1") (pinfunction "1_1") (pintype "passive"))
      (node (ref "C15") (pin "1") (pinfunction "1_1") (pintype "passive"))
      (node (ref "C16") (pin "1") (pinfunction "1_1") (pintype "passive"))
      (node (ref "C17") (pin "2") (pinfunction "2_2") (pintype "passive"))
      (node (ref "C2") (pin "2") (pinfunction "2_2") (pintype "passive"))
      (node (ref "C3") (pin "1") (pinfunction "1_1") (pintype "passive"))
      (node (ref "C4") (pin "2") (pinfunction "2_2") (pintype "passive"))
      (node (ref "C5") (pin "1") (pinfunction "1_1") (pintype "passive"))
      (node (ref "C6") (pin "2") (pinfunction "2_2") (pintype "passive"))
      (node (ref "C7") (pin "1") (pinfunction "1_1") (pintype "passive"))
      (node (ref "C8") (pin "2") (pinfunction "2_2") (pintype "passive"))
      (node (ref "C9") (pin "1") (pinfunction "1_1") (pintype "passive"))
      (node (ref "DA1") (pin "8") (pinfunction "GND_8") (pintype "power_in"))
      (node (ref "DA2") (pin "8") (pinfunction "GND_8") (pintype "power_in"))
      (node (ref "DA3") (pin "8") (pinfunction "GND_8") (pintype "power_in"))
      (node (ref "IC10") (pin "5") (pinfunction "AGND_5") (pintype "power_in"))
      (node (ref "IC11") (pin "5") (pinfunction "AGND_5") (pintype "power_in"))
      (node (ref "IC2") (pin "12") (pinfunction "+IN_12") (pintype "input"))
      (node (ref "IC2") (pin "3") (pinfunction "+IN_3") (pintype "input"))
      (node (ref "IC3") (pin "3") (pinfunction "+IN_3") (pintype "input"))
      (node (ref "IC3") (pin "5") (pinfunction "+IN_5") (pintype "input"))
      (node (ref "IC4") (pin "10") (pinfunction "+IN_10") (pintype "input"))
      (node (ref "IC4") (pin "12") (pinfunction "+IN_12") (pintype "input"))
      (node (ref "IC4") (pin "3") (pinfunction "+IN_3") (pintype "input"))
      (node (ref "IC4") (pin "5") (pinfunction "+IN_5") (pintype "input"))
      (node (ref "IC5") (pin "3") (pinfunction "+IN_3") (pintype "input"))
      (node (ref "IC5") (pin "5") (pinfunction "+IN_5") (pintype "input"))
      (node (ref "IC8") (pin "5") (pinfunction "AGND_5") (pintype "power_in"))
      (node (ref "IC9") (pin "5") (pinfunction "AGND_5") (pintype "power_in"))
      (node (ref "R12") (pin "1") (pinfunction "1_1") (pintype "passive"))
      (node (ref "R15") (pin "1") (pinfunction "1_1") (pintype "passive"))
      (node (ref "R18") (pin "1") (pinfunction "1_1") (pintype "passive"))
      (node (ref "R21") (pin "1") (pinfunction "1_1") (pintype "passive"))
      (node (ref "R24") (pin "1") (pinfunction "1_1") (pintype "passive"))
      (node (ref "R27") (pin "1") (pinfunction "1_1") (pintype "passive"))
      (node (ref "R3") (pin "1") (pinfunction "1_1") (pintype "passive"))
      (node (ref "R30") (pin "1") (pinfunction "1_1") (pintype "passive"))
      (node (ref "R33") (pin "1") (pinfunction "1_1") (pintype "passive"))
      (node (ref "R36") (pin "1") (pinfunction "1_1") (pintype "passive"))
      (node (ref "R46") (pin "2") (pinfunction "2_2") (pintype "passive"))
      (node (ref "R47") (pin "2") (pinfunction "2_2") (pintype "passive"))
      (node (ref "R49") (pin "2") (pinfunction "2_2") (pintype "passive"))
      (node (ref "R51") (pin "2") (pinfunction "2_2") (pintype "passive"))
      (node (ref "R6") (pin "1") (pinfunction "1_1") (pintype "passive"))
      (node (ref "R73") (pin "1") (pinfunction "1_1") (pintype "passive"))
      (node (ref "R74") (pin "1") (pinfunction "1_1") (pintype "passive"))
      (node (ref "R75") (pin "1") (pinfunction "1_1") (pintype "passive"))
      (node (ref "R76") (pin "1") (pinfunction "1_1") (pintype "passive"))
      (node (ref "R78") (pin "2") (pinfunction "2_2") (pintype "passive"))
      (node (ref "R9") (pin "1") (pinfunction "1_1") (pintype "passive"))
      (node (ref "U$2") (pin "7") (pinfunction "7_7") (pintype "passive"))
    )
    (net (code "103") (name "Net-(C13-Pad2)") (class "Default")
      (node (ref "C13") (pin "2") (pinfunction "2_2") (pintype "passive"))
      (node (ref "R38") (pin "1") (pinfunction "1_1") (pintype "passive"))
    )
    (net (code "104") (name "Net-(C14-Pad2)") (class "Default")
      (node (ref "C14") (pin "2") (pinfunction "2_2") (pintype "passive"))
      (node (ref "R39") (pin "1") (pinfunction "1_1") (pintype "passive"))
    )
    (net (code "105") (name "Net-(C15-Pad2)") (class "Default")
      (node (ref "C15") (pin "2") (pinfunction "2_2") (pintype "passive"))
      (node (ref "R40") (pin "1") (pinfunction "1_1") (pintype "passive"))
    )
    (net (code "106") (name "Net-(DA1B-CV2)") (class "Default")
      (node (ref "DA1") (pin "6") (pinfunction "CV2_6") (pintype "input"))
      (node (ref "R29") (pin "2") (pinfunction "2_2") (pintype "passive"))
      (node (ref "R30") (pin "2") (pinfunction "2_2") (pintype "passive"))
    )
    (net (code "107") (name "Net-(DA1B-CV3)") (class "Default")
      (node (ref "DA1") (pin "11") (pinfunction "CV3_11") (pintype "input"))
      (node (ref "R32") (pin "2") (pinfunction "2_2") (pintype "passive"))
      (node (ref "R33") (pin "2") (pinfunction "2_2") (pintype "passive"))
    )
    (net (code "108") (name "Net-(DA1B-CV4)") (class "Default")
      (node (ref "DA1") (pin "14") (pinfunction "CV4_14") (pintype "input"))
      (node (ref "R35") (pin "2") (pinfunction "2_2") (pintype "passive"))
      (node (ref "R36") (pin "2") (pinfunction "2_2") (pintype "passive"))
    )
    (net (code "109") (name "Net-(DA1B-OUT1)") (class "Default")
      (node (ref "DA1") (pin "4") (pinfunction "OUT1_4") (pintype "output"))
      (node (ref "IC2") (pin "10") (pinfunction "+IN_10") (pintype "input"))
      (node (ref "R51") (pin "1") (pinfunction "1_1") (pintype "passive"))
    )
    (net (code "110") (name "Net-(DA1B-OUT2)") (class "Default")
      (node (ref "DA1") (pin "5") (pinfunction "OUT2_5") (pintype "output"))
      (node (ref "IC2") (pin "9") (pinfunction "-IN_9") (pintype "input"))
      (node (ref "R50") (pin "2") (pinfunction "2_2") (pintype "passive"))
      (node (ref "R69") (pin "1") (pinfunction "1_1") (pintype "passive"))
    )
    (net (code "111") (name "Net-(DA1B-OUT3)") (class "Default")
      (node (ref "DA1") (pin "12") (pinfunction "OUT3_12") (pintype "output"))
      (node (ref "IC2") (pin "6") (pinfunction "-IN_6") (pintype "input"))
      (node (ref "R52") (pin "2") (pinfunction "2_2") (pintype "passive"))
    )
    (net (code "112") (name "Net-(DA1B-OUT4)") (class "Default")
      (node (ref "DA1") (pin "13") (pinfunction "OUT4_13") (pintype "output"))
      (node (ref "IC2") (pin "5") (pinfunction "+IN_5") (pintype "input"))
      (node (ref "R49") (pin "1") (pinfunction "1_1") (pintype "passive"))
    )
    (net (code "113") (name "Net-(DA1B-VREF)") (class "Default")
      (node (ref "DA1") (pin "1") (pinfunction "VREF_1") (pintype "output"))
      (node (ref "R40") (pin "2") (pinfunction "2_2") (pintype "passive"))
    )
    (net (code "114") (name "Net-(DA2B-CV2)") (class "Default")
      (node (ref "DA2") (pin "6") (pinfunction "CV2_6") (pintype "input"))
      (node (ref "R5") (pin "2") (pinfunction "2_2") (pintype "passive"))
      (node (ref "R6") (pin "2") (pinfunction "2_2") (pintype "passive"))
    )
    (net (code "115") (name "Net-(DA2B-CV3)") (class "Default")
      (node (ref "DA2") (pin "11") (pinfunction "CV3_11") (pintype "input"))
      (node (ref "R8") (pin "2") (pinfunction "2_2") (pintype "passive"))
      (node (ref "R9") (pin "2") (pinfunction "2_2") (pintype "passive"))
    )
    (net (code "116") (name "Net-(DA2B-CV4)") (class "Default")
      (node (ref "DA2") (pin "14") (pinfunction "CV4_14") (pintype "input"))
      (node (ref "R11") (pin "2") (pinfunction "2_2") (pintype "passive"))
      (node (ref "R12") (pin "2") (pinfunction "2_2") (pintype "passive"))
    )
    (net (code "117") (name "Net-(DA2B-VREF)") (class "Default")
      (node (ref "DA2") (pin "1") (pinfunction "VREF_1") (pintype "output"))
      (node (ref "R38") (pin "2") (pinfunction "2_2") (pintype "passive"))
    )
    (net (code "118") (name "Net-(DA3B-CV2)") (class "Default")
      (node (ref "DA3") (pin "6") (pinfunction "CV2_6") (pintype "input"))
      (node (ref "R17") (pin "2") (pinfunction "2_2") (pintype "passive"))
      (node (ref "R18") (pin "2") (pinfunction "2_2") (pintype "passive"))
    )
    (net (code "119") (name "Net-(DA3B-CV3)") (class "Default")
      (node (ref "DA3") (pin "11") (pinfunction "CV3_11") (pintype "input"))
      (node (ref "R20") (pin "2") (pinfunction "2_2") (pintype "passive"))
      (node (ref "R21") (pin "2") (pinfunction "2_2") (pintype "passive"))
    )
    (net (code "120") (name "Net-(DA3B-CV4)") (class "Default")
      (node (ref "DA3") (pin "14") (pinfunction "CV4_14") (pintype "input"))
      (node (ref "R23") (pin "2") (pinfunction "2_2") (pintype "passive"))
      (node (ref "R24") (pin "2") (pinfunction "2_2") (pintype "passive"))
    )
    (net (code "121") (name "Net-(DA3B-OUT2)") (class "Default")
      (node (ref "DA3") (pin "5") (pinfunction "OUT2_5") (pintype "output"))
      (node (ref "IC6") (pin "3") (pinfunction "+IN_3") (pintype "input"))
      (node (ref "R46") (pin "1") (pinfunction "1_1") (pintype "passive"))
    )
    (net (code "122") (name "Net-(DA3B-VREF)") (class "Default")
      (node (ref "DA3") (pin "1") (pinfunction "VREF_1") (pintype "output"))
      (node (ref "R39") (pin "2") (pinfunction "2_2") (pintype "passive"))
    )
    (net (code "123") (name "unconnected-(IC1-~{INT}-Pad1)") (class "Default")
      (node (ref "IC1") (pin "1") (pinfunction "~{INT}_1") (pintype "bidirectional"))
    )
  )
)
